# EC_Sensor2.net
KiCad netlist of a schematic drawn in Altium Designer
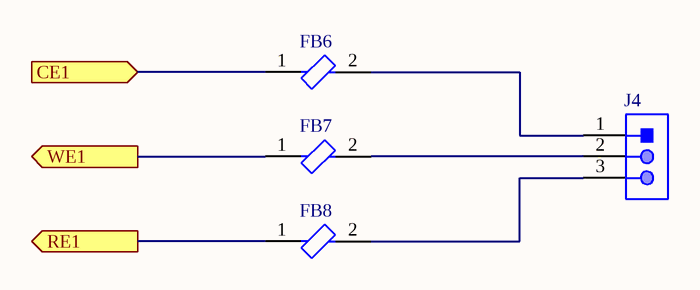
[diagram p0: EC_Sensor2.SchDoc]

(export (version "E")
  (design (tool "Eeschema 10.0.6"))
  (components
    (comp (ref "FB6")
      (value "BLM15PD600SN1D")
      (footprint "FP-BLM15-0_05-d0_7-IPC_B")
      (description "Chip Ferrite Bead, 0402, 60Ω @ 100MHz, 0.06Ω, 25%, 1.7A")
      (fields (field (name "TOLERANCE") "25%"))
      (libsource (lib "Altium Content Vault") (part "5f30dd21d616792df468990f7003faa"))
    )
    (comp (ref "FB7")
      (value "BLM15PD600SN1D")
      (footprint "FP-BLM15-0_05-d0_7-IPC_B")
      (description "Chip Ferrite Bead, 0402, 60Ω @ 100MHz, 0.06Ω, 25%, 1.7A")
      (fields (field (name "TOLERANCE") "25%"))
      (libsource (lib "Altium Content Vault") (part "5f30dd21d616792df468990f7003faa"))
    )
    (comp (ref "FB8")
      (value "BLM15PD600SN1D")
      (footprint "FP-BLM15-0_05-d0_7-IPC_B")
      (description "Chip Ferrite Bead, 0402, 60Ω @ 100MHz, 0.06Ω, 25%, 1.7A")
      (fields (field (name "TOLERANCE") "25%"))
      (libsource (lib "Altium Content Vault") (part "5f30dd21d616792df468990f7003faa"))
    )
    (comp (ref "J4")
      (value "61300311021")
      (footprint "61300311021")
      (description "THT Angled Pin Header WR-PHD, Pitch 2.54 mm, Single Row, 3 pins")
      (fields (field (name "MANUFACTURER") "Wurth Elektronik") (field (name "PUBLISHER") "WurthElektronik"))
      (libsource (lib "Altium Content Vault") (part "WE-CN-1P-M-R3"))
    )
  )
  (nets
    (net (code "1") (name "/CE1") (class "Default")
      (node (ref "FB6") (pin "1") (pinfunction "1_1") (pintype "passive"))
    )
    (net (code "2") (name "/RE1") (class "Default")
      (node (ref "FB8") (pin "1") (pinfunction "1_1") (pintype "passive"))
    )
    (net (code "3") (name "/WE1") (class "Default")
      (node (ref "FB7") (pin "1") (pinfunction "1_1") (pintype "passive"))
    )
    (net (code "4") (name "Net-(FB6-Pad2)") (class "Default")
      (node (ref "FB6") (pin "2") (pinfunction "2_2") (pintype "passive"))
      (node (ref "J4") (pin "1") (pinfunction "1_1") (pintype "passive"))
    )
    (net (code "5") (name "Net-(FB7-Pad2)") (class "Default")
      (node (ref "FB7") (pin "2") (pinfunction "2_2") (pintype "passive"))
      (node (ref "J4") (pin "2") (pinfunction "2_2") (pintype "passive"))
    )
    (net (code "6") (name "Net-(FB8-Pad2)") (class "Default")
      (node (ref "FB8") (pin "2") (pinfunction "2_2") (pintype "passive"))
      (node (ref "J4") (pin "3") (pinfunction "3_3") (pintype "passive"))
    )
  )
)
